# 24Vreg.net
KiCad netlist of a schematic drawn in Altium Designer
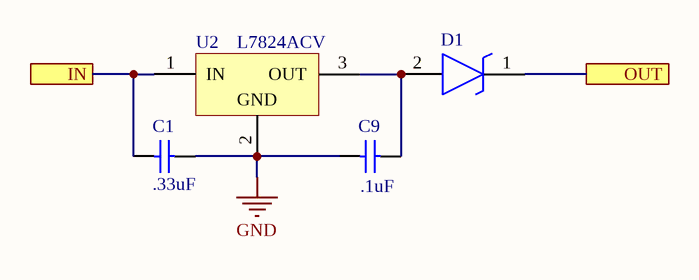
[diagram p0: 24Vreg.SchDoc]

(export (version "E")
  (design (tool "Eeschema 10.0.6"))
  (components
    (comp (ref "C1")
      (value ".33uF")
      (footprint "CAPC2013X140X50ML20T25")
      (fields
        (field (name "MANUFACTURER") "AVX Interconnect / Elco")
        (field (name "PART NUMBER") "08053G334ZAT2A")
      )
      (libsource (lib "Altium Content Vault") (part "CAP"))
    )
    (comp (ref "C9")
      (value ".1uF")
      (footprint "CAPC2013X135X45ML10T25")
      (description "Chip Capacitor, 0.1 uF, +/- 10%, 50 V, -55 to 125 degC, 0805 (2012 Metric), RoHS, Tape and Reel")
      (fields (field (name "VOLTAGE") "50V") (field (name "TOLERANCE") "10%"))
      (libsource (lib "Altium Content Vault") (part "CAP-NP-2"))
    )
    (comp (ref "D1")
      (value "PMEG3020DEP,115")
      (footprint "SamacSys:PMEG3050EP115")
      (description "Schottky Diode")
      (fields
        (field (name "MOUSER PART NUMBER") "771-PMEG3020DEP115")
        (field (name "RS PART NUMBER") "1513202")
      )
      (libsource (lib "*") (part "PMEG3020DEP,115"))
    )
    (comp (ref "U2")
      (value "L7824ACV")
      (footprint "TO220")
      (description "Positive Voltage Regulator, 24V, 3-Pin TO-220")
      (libsource (lib "Altium Content Vault") (part "PM-REG-L4940-SIL3"))
    )
  )
  (nets
    (net (code "1") (name "/IN") (class "Default")
      (node (ref "C1") (pin "1") (pinfunction "1_1") (pintype "passive"))
      (node (ref "U2") (pin "1") (pinfunction "IN_1") (pintype "power_in"))
    )
    (net (code "2") (name "/OUT") (class "Default")
      (node (ref "D1") (pin "1") (pinfunction "K_1") (pintype "passive"))
    )
    (net (code "3") (name "GND") (class "Default")
      (node (ref "C1") (pin "2") (pinfunction "2_2") (pintype "passive"))
      (node (ref "C9") (pin "1") (pinfunction "1_1") (pintype "passive"))
      (node (ref "U2") (pin "2") (pinfunction "GND_2") (pintype "power_in"))
    )
    (net (code "4") (name "Net-(D1-A)") (class "Default")
      (node (ref "C9") (pin "2") (pinfunction "2_2") (pintype "passive"))
      (node (ref "D1") (pin "2") (pinfunction "A_2") (pintype "passive"))
      (node (ref "U2") (pin "3") (pinfunction "OUT_3") (pintype "power_in"))
    )
  )
)
